# SOIC_TSSOP-16_300mil_DIP.net
KiCad netlist of a schematic drawn in EAGLE
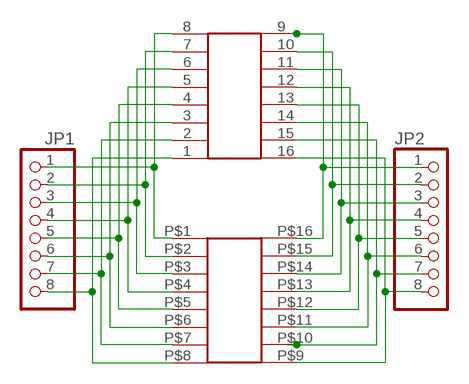
[diagram p0: schematic, sheet 1]

(export (version "E")
  (design (tool "Eeschema 10.0.6"))
  (components
    (comp (ref "JP1")
      (value "PINHD-1X8")
      (footprint "eagle-import:1X08")
      (libsource (lib "eagle-import") (part "PINHD-1X8"))
    )
    (comp (ref "JP2")
      (value "PINHD-1X8")
      (footprint "eagle-import:1X08")
      (libsource (lib "eagle-import") (part "PINHD-1X8"))
    )
    (comp (ref "U$1")
      (value "SMD-16SOIC")
      (footprint "eagle-import:SO-16NMW")
      (libsource (lib "eagle-import") (part "SMD-16SOIC"))
    )
    (comp (ref "U$2")
      (value "SMD-16TSSOP")
      (footprint "eagle-import:TSSOP-16NM")
      (libsource (lib "eagle-import") (part "SMD-16TSSOP"))
    )
  )
  (nets
    (net (code "1") (name "Net-(U$2-P$1)") (class "Default")
      (node (ref "JP1") (pin "8") (pinfunction "8_8") (pintype "passive"))
      (node (ref "U$1") (pin "P$8") (pinfunction "P$8_P$8") (pintype "bidirectional"))
      (node (ref "U$2") (pin "1") (pinfunction "P$1_1") (pintype "bidirectional"))
    )
    (net (code "2") (name "Net-(U$2-P$2)") (class "Default")
      (node (ref "JP1") (pin "7") (pinfunction "7_7") (pintype "passive"))
      (node (ref "U$1") (pin "P$7") (pinfunction "P$7_P$7") (pintype "bidirectional"))
      (node (ref "U$2") (pin "2") (pinfunction "P$2_2") (pintype "bidirectional"))
    )
    (net (code "3") (name "Net-(U$2-P$3)") (class "Default")
      (node (ref "JP1") (pin "6") (pinfunction "6_6") (pintype "passive"))
      (node (ref "U$1") (pin "P$6") (pinfunction "P$6_P$6") (pintype "bidirectional"))
      (node (ref "U$2") (pin "3") (pinfunction "P$3_3") (pintype "bidirectional"))
    )
    (net (code "4") (name "Net-(U$2-P$4)") (class "Default")
      (node (ref "JP1") (pin "5") (pinfunction "5_5") (pintype "passive"))
      (node (ref "U$1") (pin "P$5") (pinfunction "P$5_P$5") (pintype "bidirectional"))
      (node (ref "U$2") (pin "4") (pinfunction "P$4_4") (pintype "bidirectional"))
    )
    (net (code "5") (name "Net-(U$2-P$5)") (class "Default")
      (node (ref "JP1") (pin "4") (pinfunction "4_4") (pintype "passive"))
      (node (ref "U$1") (pin "P$4") (pinfunction "P$4_P$4") (pintype "bidirectional"))
      (node (ref "U$2") (pin "5") (pinfunction "P$5_5") (pintype "bidirectional"))
    )
    (net (code "6") (name "Net-(U$2-P$6)") (class "Default")
      (node (ref "JP1") (pin "3") (pinfunction "3_3") (pintype "passive"))
      (node (ref "U$1") (pin "P$3") (pinfunction "P$3_P$3") (pintype "bidirectional"))
      (node (ref "U$2") (pin "6") (pinfunction "P$6_6") (pintype "bidirectional"))
    )
    (net (code "7") (name "Net-(U$2-P$7)") (class "Default")
      (node (ref "JP1") (pin "2") (pinfunction "2_2") (pintype "passive"))
      (node (ref "U$1") (pin "P$2") (pinfunction "P$2_P$2") (pintype "bidirectional"))
      (node (ref "U$2") (pin "7") (pinfunction "P$7_7") (pintype "bidirectional"))
    )
    (net (code "8") (name "Net-(U$2-P$8)") (class "Default")
      (node (ref "JP1") (pin "1") (pinfunction "1_1") (pintype "passive"))
      (node (ref "U$1") (pin "P$1") (pinfunction "P$1_P$1") (pintype "bidirectional"))
      (node (ref "U$2") (pin "8") (pinfunction "P$8_8") (pintype "bidirectional"))
    )
    (net (code "9") (name "Net-(U$2-P$9)") (class "Default")
      (node (ref "JP2") (pin "1") (pinfunction "1_1") (pintype "passive"))
      (node (ref "U$1") (pin "P$16") (pinfunction "P$16_P$16") (pintype "bidirectional"))
      (node (ref "U$2") (pin "9") (pinfunction "P$9_9") (pintype "bidirectional"))
    )
    (net (code "10") (name "Net-(U$2-P$10)") (class "Default")
      (node (ref "JP2") (pin "2") (pinfunction "2_2") (pintype "passive"))
      (node (ref "U$1") (pin "P$15") (pinfunction "P$15_P$15") (pintype "bidirectional"))
      (node (ref "U$2") (pin "10") (pinfunction "P$10_10") (pintype "bidirectional"))
    )
    (net (code "11") (name "Net-(U$2-P$11)") (class "Default")
      (node (ref "JP2") (pin "3") (pinfunction "3_3") (pintype "passive"))
      (node (ref "U$1") (pin "P$14") (pinfunction "P$14_P$14") (pintype "bidirectional"))
      (node (ref "U$2") (pin "11") (pinfunction "P$11_11") (pintype "bidirectional"))
    )
    (net (code "12") (name "Net-(U$2-P$12)") (class "Default")
      (node (ref "JP2") (pin "4") (pinfunction "4_4") (pintype "passive"))
      (node (ref "U$1") (pin "P$13") (pinfunction "P$13_P$13") (pintype "bidirectional"))
      (node (ref "U$2") (pin "12") (pinfunction "P$12_12") (pintype "bidirectional"))
    )
    (net (code "13") (name "Net-(U$2-P$13)") (class "Default")
      (node (ref "JP2") (pin "5") (pinfunction "5_5") (pintype "passive"))
      (node (ref "U$1") (pin "P$12") (pinfunction "P$12_P$12") (pintype "bidirectional"))
      (node (ref "U$2") (pin "13") (pinfunction "P$13_13") (pintype "bidirectional"))
    )
    (net (code "14") (name "Net-(U$2-P$14)") (class "Default")
      (node (ref "JP2") (pin "6") (pinfunction "6_6") (pintype "passive"))
      (node (ref "U$1") (pin "P$11") (pinfunction "P$11_P$11") (pintype "bidirectional"))
      (node (ref "U$2") (pin "14") (pinfunction "P$14_14") (pintype "bidirectional"))
    )
    (net (code "15") (name "Net-(U$2-P$15)") (class "Default")
      (node (ref "JP2") (pin "7") (pinfunction "7_7") (pintype "passive"))
      (node (ref "U$1") (pin "P$10") (pinfunction "P$10_P$10") (pintype "bidirectional"))
      (node (ref "U$2") (pin "15") (pinfunction "P$15_15") (pintype "bidirectional"))
    )
    (net (code "16") (name "Net-(U$2-P$16)") (class "Default")
      (node (ref "JP2") (pin "8") (pinfunction "8_8") (pintype "passive"))
      (node (ref "U$1") (pin "P$9") (pinfunction "P$9_P$9") (pintype "bidirectional"))
      (node (ref "U$2") (pin "16") (pinfunction "P$16_16") (pintype "bidirectional"))
    )
  )
)
